# current_meas.net
KiCad netlist of a schematic drawn in EAGLE
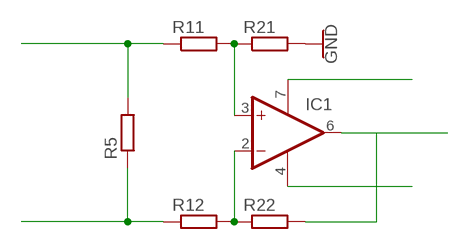
[diagram p0: schematic, sheet 1]

(export (version "E")
  (design (tool "Eeschema 10.0.6"))
  (components
    (comp (ref "IC1")
      (value "1AMP_P7+4D")
      (footprint "eagle-import:SO08")
      (libsource (lib "eagle-import") (part "1AMP_P7+4D"))
    )
    (comp (ref "R5")
      (value "R-EU_M1406")
      (footprint "eagle-import:M1406")
      (libsource (lib "eagle-import") (part "R-EU_M1406"))
    )
    (comp (ref "R11")
      (value "R-EU_M1406")
      (footprint "eagle-import:M1406")
      (libsource (lib "eagle-import") (part "R-EU_M1406"))
    )
    (comp (ref "R12")
      (value "R-EU_M1406")
      (footprint "eagle-import:M1406")
      (libsource (lib "eagle-import") (part "R-EU_M1406"))
    )
    (comp (ref "R21")
      (value "R-EU_M1406")
      (footprint "eagle-import:M1406")
      (libsource (lib "eagle-import") (part "R-EU_M1406"))
    )
    (comp (ref "R22")
      (value "R-EU_M1406")
      (footprint "eagle-import:M1406")
      (libsource (lib "eagle-import") (part "R-EU_M1406"))
    )
  )
  (nets
    (net (code "1") (name "GND") (class "Default")
      (node (ref "R21") (pin "2") (pinfunction "2_2") (pintype "passive"))
    )
    (net (code "2") (name "Net-(IC1-+IN)") (class "Default")
      (node (ref "IC1") (pin "3") (pinfunction "+IN_3") (pintype "input"))
      (node (ref "R11") (pin "2") (pinfunction "2_2") (pintype "passive"))
      (node (ref "R21") (pin "1") (pinfunction "1_1") (pintype "passive"))
    )
    (net (code "3") (name "Net-(IC1--IN)") (class "Default")
      (node (ref "IC1") (pin "2") (pinfunction "-IN_2") (pintype "input"))
      (node (ref "R12") (pin "2") (pinfunction "2_2") (pintype "passive"))
      (node (ref "R22") (pin "1") (pinfunction "1_1") (pintype "passive"))
    )
    (net (code "4") (name "Net-(IC1-OUT)") (class "Default")
      (node (ref "IC1") (pin "6") (pinfunction "OUT_6") (pintype "output"))
      (node (ref "R22") (pin "2") (pinfunction "2_2") (pintype "passive"))
    )
    (net (code "5") (name "Net-(R11-Pad1)") (class "Default")
      (node (ref "R11") (pin "1") (pinfunction "1_1") (pintype "passive"))
      (node (ref "R5") (pin "2") (pinfunction "2_2") (pintype "passive"))
    )
    (net (code "6") (name "Net-(R12-Pad1)") (class "Default")
      (node (ref "R12") (pin "1") (pinfunction "1_1") (pintype "passive"))
      (node (ref "R5") (pin "1") (pinfunction "1_1") (pintype "passive"))
    )
    (net (code "7") (name "unconnected-(IC1-V+-Pad7)") (class "Default")
      (node (ref "IC1") (pin "7") (pinfunction "V+_7") (pintype "power_in"))
    )
    (net (code "8") (name "unconnected-(IC1-V--Pad4)") (class "Default")
      (node (ref "IC1") (pin "4") (pinfunction "V-_4") (pintype "power_in"))
    )
  )
)
